# 08-I225-1.net
KiCad netlist of a schematic drawn in Altium Designer
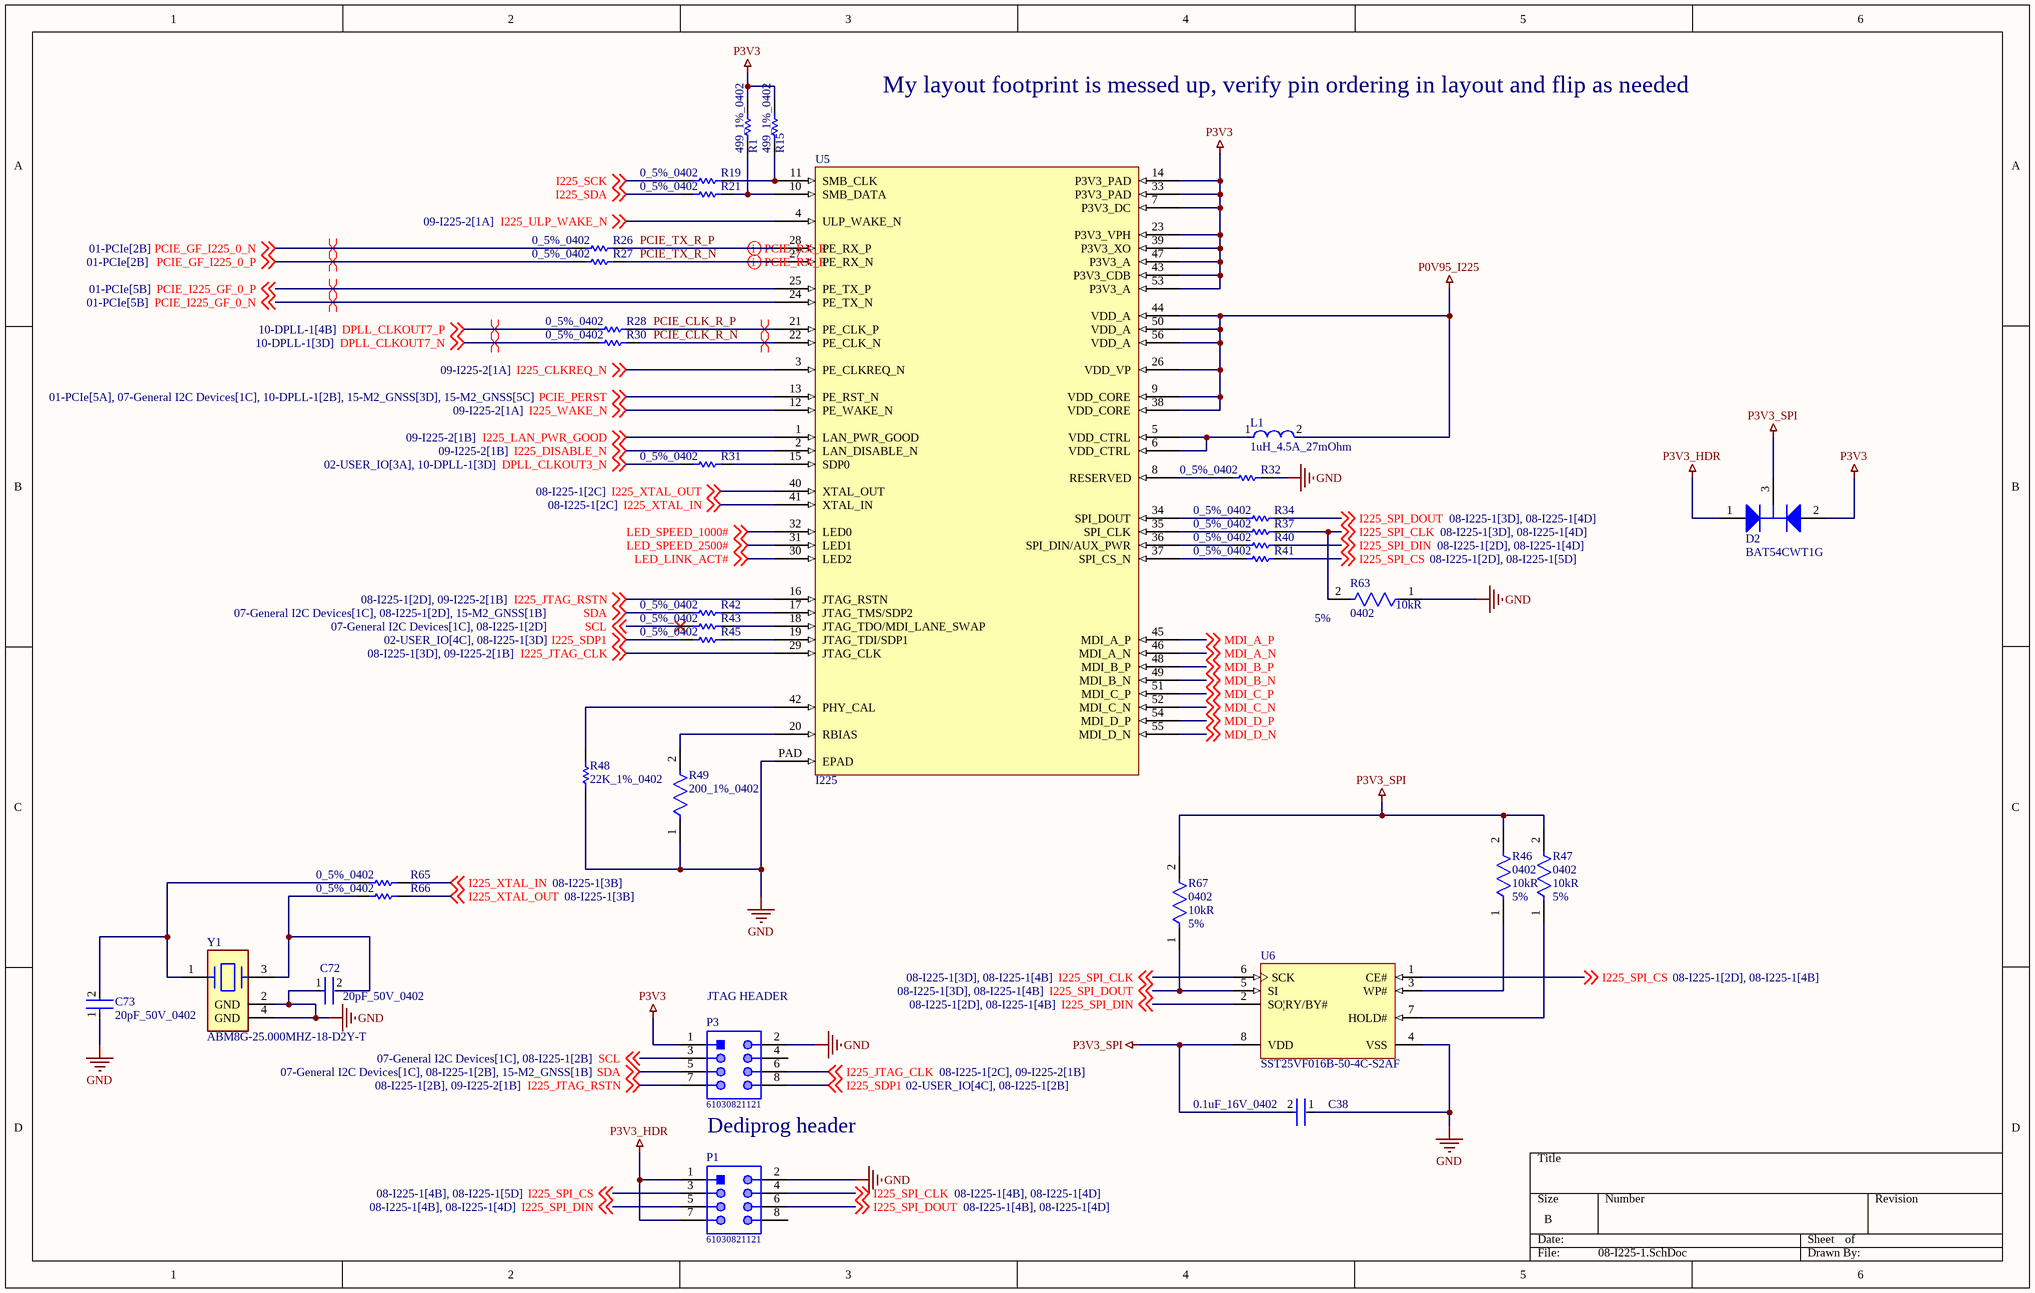
[diagram p0: 08-I225-1.SchDoc]

(export (version "E")
  (design (tool "Eeschema 10.0.6"))
  (components
    (comp (ref "C38")
      (value "0.1uF_16V_0402")
      (footprint "FP-GRM15-MFG")
      (description "CAP CER 0.1UF 16V X7R 0402")
      (fields (field (name "MANUFACTURER PART NUMBER") "GRM155R71C104KA88D") (field (name "TOLERANCE") "10%"))
      (libsource (lib "Altium Content Vault") (part "236180d848d6139a670b325ea6854c9"))
    )
    (comp (ref "C72")
      (value "20pF_50V_0402")
      (footprint "FP-C0402-BB-MFG")
      (description "CAP CER 20PF 50V 5% NP0 0402")
      (fields
        (field (name "MANUFACTURER PART NUMBER") "C0402C200J5GACTU")
        (field (name "OCTOPART") "https://octopart.com/c0402c200j5gactu-kemet-9143900")
      )
      (libsource (lib "Altium Content Vault") (part "b4654b650e69147ec39a6b967a45e02"))
    )
    (comp (ref "C73")
      (value "20pF_50V_0402")
      (footprint "FP-C0402-BB-MFG")
      (description "CAP CER 20PF 50V 5% NP0 0402")
      (fields
        (field (name "MANUFACTURER PART NUMBER") "C0402C200J5GACTU")
        (field (name "OCTOPART") "https://octopart.com/c0402c200j5gactu-kemet-9143900")
      )
      (libsource (lib "Altium Content Vault") (part "b4654b650e69147ec39a6b967a45e02"))
    )
    (comp (ref "D2")
      (value "BAT54CWT1G")
      (footprint "ONSC-SOT-323-3-419-04_V")
      (description "Dual Series Cathode Schottky Barrier Diodes, 3-Pin SOT-323, Pb-Free, Tape and Reel")
      (fields (field (name "MANUFACTURER") "On Semiconductor"))
      (libsource (lib "Altium Content Vault") (part "ONSC-D-A1A2K3-3"))
    )
    (comp (ref "L1")
      (value "1uH_4.5A_27mOhm")
      (footprint "FP-IHLP-1616BZ-FP_1_8545x-MFG")
      (description "Fixed Inductors Commercial Low DCR Series SMT 1uH 4.5A 27mΩ 20%")
      (fields (field (name "TOLERANCE") "20%"))
      (libsource (lib "Altium Content Vault") (part "725321dda6339637d4d059423bc1c3c"))
    )
    (comp (ref "P1")
      (value "61030821121")
      (footprint "61030821121")
      (description "SMT Vertical Pin Header WR-PHD, Pitch 2.54 mm, Dual Row, 8 pins")
      (fields (field (name "MANUFACTURER") "Wurth Elektronik") (field (name "PUBLISHER") "WurthElektronik"))
      (libsource (lib "Altium Content Vault") (part "WE-CN-2P-M-R8"))
    )
    (comp (ref "P3")
      (value "61030821121")
      (footprint "61030821121")
      (description "SMT Vertical Pin Header WR-PHD, Pitch 2.54 mm, Dual Row, 8 pins")
      (fields (field (name "MANUFACTURER") "Wurth Elektronik") (field (name "PUBLISHER") "WurthElektronik"))
      (libsource (lib "Altium Content Vault") (part "WE-CN-2P-M-R8"))
    )
    (comp (ref "R1")
      (value "499_1%_0402")
      (footprint "RESC1005X40X25LL05T05")
      (fields (field (name "MANUFACTURER") "Panasonic") (field (name "PART NUMBER") "ERJ-2RKF4990X"))
      (libsource (lib "Altium Content Vault") (part "RES"))
    )
    (comp (ref "R15")
      (value "499_1%_0402")
      (footprint "RESC1005X40X25LL05T05")
      (fields (field (name "MANUFACTURER") "Panasonic") (field (name "PART NUMBER") "ERJ-2RKF4990X"))
      (libsource (lib "Altium Content Vault") (part "RES"))
    )
    (comp (ref "R19")
      (value "0_5%_0402")
      (footprint "RESC1005X40X25LL10T10")
      (fields (field (name "MANUFACTURER") "KOA Speer") (field (name "PART NUMBER") "RK73Z1ETTP"))
      (libsource (lib "Altium Content Vault") (part "RES"))
    )
    (comp (ref "R21")
      (value "0_5%_0402")
      (footprint "RESC1005X40X25LL10T10")
      (fields (field (name "MANUFACTURER") "KOA Speer") (field (name "PART NUMBER") "RK73Z1ETTP"))
      (libsource (lib "Altium Content Vault") (part "RES"))
    )
    (comp (ref "R26")
      (value "0_5%_0402")
      (footprint "RESC1005X40X25LL10T10")
      (fields (field (name "MANUFACTURER") "KOA Speer") (field (name "PART NUMBER") "RK73Z1ETTP"))
      (libsource (lib "Altium Content Vault") (part "RES"))
    )
    (comp (ref "R27")
      (value "0_5%_0402")
      (footprint "RESC1005X40X25LL10T10")
      (fields (field (name "MANUFACTURER") "KOA Speer") (field (name "PART NUMBER") "RK73Z1ETTP"))
      (libsource (lib "Altium Content Vault") (part "RES"))
    )
    (comp (ref "R28")
      (value "0_5%_0402")
      (footprint "RESC1005X40X25LL10T10")
      (fields (field (name "MANUFACTURER") "KOA Speer") (field (name "PART NUMBER") "RK73Z1ETTP"))
      (libsource (lib "Altium Content Vault") (part "RES"))
    )
    (comp (ref "R30")
      (value "0_5%_0402")
      (footprint "RESC1005X40X25LL10T10")
      (fields (field (name "MANUFACTURER") "KOA Speer") (field (name "PART NUMBER") "RK73Z1ETTP"))
      (libsource (lib "Altium Content Vault") (part "RES"))
    )
    (comp (ref "R31")
      (value "0_5%_0402")
      (footprint "RESC1005X40X25LL10T10")
      (fields (field (name "MANUFACTURER") "KOA Speer") (field (name "PART NUMBER") "RK73Z1ETTP"))
      (libsource (lib "Altium Content Vault") (part "RES"))
    )
    (comp (ref "R32")
      (value "0_5%_0402")
      (footprint "RESC1005X40X25LL10T10")
      (fields (field (name "MANUFACTURER") "KOA Speer") (field (name "PART NUMBER") "RK73Z1ETTP"))
      (libsource (lib "Altium Content Vault") (part "RES"))
    )
    (comp (ref "R34")
      (value "0_5%_0402")
      (footprint "RESC1005X40X25LL10T10")
      (fields (field (name "MANUFACTURER") "KOA Speer") (field (name "PART NUMBER") "RK73Z1ETTP"))
      (libsource (lib "Altium Content Vault") (part "RES"))
    )
    (comp (ref "R37")
      (value "0_5%_0402")
      (footprint "RESC1005X40X25LL10T10")
      (fields (field (name "MANUFACTURER") "KOA Speer") (field (name "PART NUMBER") "RK73Z1ETTP"))
      (libsource (lib "Altium Content Vault") (part "RES"))
    )
    (comp (ref "R40")
      (value "0_5%_0402")
      (footprint "RESC1005X40X25LL10T10")
      (fields (field (name "MANUFACTURER") "KOA Speer") (field (name "PART NUMBER") "RK73Z1ETTP"))
      (libsource (lib "Altium Content Vault") (part "RES"))
    )
    (comp (ref "R41")
      (value "0_5%_0402")
      (footprint "RESC1005X40X25LL10T10")
      (fields (field (name "MANUFACTURER") "KOA Speer") (field (name "PART NUMBER") "RK73Z1ETTP"))
      (libsource (lib "Altium Content Vault") (part "RES"))
    )
    (comp (ref "R42")
      (value "0_5%_0402")
      (footprint "RESC1005X40X25LL10T10")
      (fields (field (name "MANUFACTURER") "KOA Speer") (field (name "PART NUMBER") "RK73Z1ETTP"))
      (libsource (lib "Altium Content Vault") (part "RES"))
    )
    (comp (ref "R43")
      (value "0_5%_0402")
      (footprint "RESC1005X40X25LL10T10")
      (fields (field (name "MANUFACTURER") "KOA Speer") (field (name "PART NUMBER") "RK73Z1ETTP"))
      (libsource (lib "Altium Content Vault") (part "RES"))
    )
    (comp (ref "R45")
      (value "0_5%_0402")
      (footprint "RESC1005X40X25LL10T10")
      (fields (field (name "MANUFACTURER") "KOA Speer") (field (name "PART NUMBER") "RK73Z1ETTP"))
      (libsource (lib "Altium Content Vault") (part "RES"))
    )
    (comp (ref "R46")
      (value "CRCW040210K0JNED")
      (footprint "FP-CRCW0402-e3-IPC_B")
      (description "RES Thick Film, 10kΩ, 5%, 0.063W, 200ppm/°C, 0402")
      (fields
        (field (name "CASE/PACKAGE") "0402")
        (field (name "RESISTANCE") "10kR")
        (field (name "TOLERANCE") "5%")
      )
      (libsource (lib "Altium Content Vault") (part "1029c3af85768c4190bb7ad29bc67b5"))
    )
    (comp (ref "R47")
      (value "CRCW040210K0JNED")
      (footprint "FP-CRCW0402-e3-IPC_B")
      (description "RES Thick Film, 10kΩ, 5%, 0.063W, 200ppm/°C, 0402")
      (fields
        (field (name "CASE/PACKAGE") "0402")
        (field (name "RESISTANCE") "10kR")
        (field (name "TOLERANCE") "5%")
      )
      (libsource (lib "Altium Content Vault") (part "1029c3af85768c4190bb7ad29bc67b5"))
    )
    (comp (ref "R48")
      (value "22K_1%_0402")
      (footprint "RESC1005X40X25NL05T05")
      (fields (field (name "PART NUMBER") "CRCW040222K0FKED") (field (name "MANUFACTURER") "Vishay Dale"))
      (libsource (lib "Altium Content Vault") (part "RES"))
    )
    (comp (ref "R49")
      (value "200_1%_0402")
      (footprint "FP-CRCW0402-e3-IPC_C")
      (description "RES Thick Film, 200Ω, 1%, 0.063W, 100ppm/°C, 0402")
      (fields (field (name "TOLERANCE") "1%"))
      (libsource (lib "Altium Content Vault") (part "1029c3af85768c4190bb7ad29bc67b5"))
    )
    (comp (ref "R63")
      (value "CRCW040210K0JNED")
      (footprint "FP-CRCW0402-e3-IPC_B")
      (description "RES Thick Film, 10kΩ, 5%, 0.063W, 200ppm/°C, 0402")
      (fields
        (field (name "CASE/PACKAGE") "0402")
        (field (name "RESISTANCE") "10kR")
        (field (name "TOLERANCE") "5%")
      )
      (libsource (lib "Altium Content Vault") (part "1029c3af85768c4190bb7ad29bc67b5"))
    )
    (comp (ref "R65")
      (value "0_5%_0402")
      (footprint "RESC1005X40X25LL10T10")
      (fields (field (name "MANUFACTURER") "KOA Speer") (field (name "PART NUMBER") "RK73Z1ETTP"))
      (libsource (lib "Altium Content Vault") (part "RES"))
    )
    (comp (ref "R66")
      (value "0_5%_0402")
      (footprint "RESC1005X40X25LL10T10")
      (fields (field (name "MANUFACTURER") "KOA Speer") (field (name "PART NUMBER") "RK73Z1ETTP"))
      (libsource (lib "Altium Content Vault") (part "RES"))
    )
    (comp (ref "R67")
      (value "CRCW040210K0JNED")
      (footprint "FP-CRCW0402-e3-IPC_B")
      (description "RES Thick Film, 10kΩ, 5%, 0.063W, 200ppm/°C, 0402")
      (fields
        (field (name "CASE/PACKAGE") "0402")
        (field (name "RESISTANCE") "10kR")
        (field (name "TOLERANCE") "5%")
      )
      (libsource (lib "Altium Content Vault") (part "1029c3af85768c4190bb7ad29bc67b5"))
    )
    (comp (ref "U5") (value "I225") (footprint "I225 QFN56") (libsource (lib "TimeStick_Lib") (part "I225")))
    (comp (ref "U6")
      (value "SST25VF016B-50-4C-S2AF")
      (footprint "MCHP-SOIC-S2A8_M")
      (description "16 Mbit SPI Serial Flash, 2.7 to 3.6 V, 50 MHz, 0 to 70 degC, 8-pin SOIC (S2A8), Tube")
      (fields (field (name "MANUFACTURER") "Microchip"))
      (libsource (lib "Altium Content Vault") (part "MCHP-SST25VFXXXB-SOIX-8"))
    )
    (comp (ref "Y1")
      (value "ABM8G-25.000MHZ-18-D2Y-T")
      (footprint "FP-ABM8G-MFG")
      (description "CRYSTAL 25.0000MHZ 18PF SMD")
      (fields
        (field (name "MANUFACTURER") "Abracon")
        (field (name "OCTOPART") "https://octopart.com/abm8g-25.000mhz-18-d2y-t-abracon-12676602")
      )
      (libsource (lib "Altium Content Vault") (part "82af6c543cb7a88a4cbd02a3a01c293"))
    )
  )
  (nets
    (net (code "1") (name "/PCIE_CLK_R_N") (class "Default")
      (node (ref "R30") (pin "2") (pinfunction "2_2") (pintype "passive"))
      (node (ref "U5") (pin "22") (pinfunction "PE_CLK_N_22") (pintype "input"))
    )
    (net (code "2") (name "/PCIE_CLK_R_P") (class "Default")
      (node (ref "R28") (pin "2") (pinfunction "2_2") (pintype "passive"))
      (node (ref "U5") (pin "21") (pinfunction "PE_CLK_P_21") (pintype "input"))
    )
    (net (code "3") (name "/PCIE_TX_R_N") (class "Default")
      (node (ref "R27") (pin "2") (pinfunction "2_2") (pintype "passive"))
      (node (ref "U5") (pin "27") (pinfunction "PE_RX_N_27") (pintype "input"))
    )
    (net (code "4") (name "/PCIE_TX_R_P") (class "Default")
      (node (ref "R26") (pin "2") (pinfunction "2_2") (pintype "passive"))
      (node (ref "U5") (pin "28") (pinfunction "PE_RX_P_28") (pintype "input"))
    )
    (net (code "5") (name "DPLL_CLKOUT3_N") (class "Default")
      (node (ref "R31") (pin "1") (pinfunction "1_1") (pintype "passive"))
    )
    (net (code "6") (name "DPLL_CLKOUT7_N") (class "Default")
      (node (ref "R30") (pin "1") (pinfunction "1_1") (pintype "passive"))
    )
    (net (code "7") (name "DPLL_CLKOUT7_P") (class "Default")
      (node (ref "R28") (pin "1") (pinfunction "1_1") (pintype "passive"))
    )
    (net (code "8") (name "GND") (class "Default")
      (node (ref "C38") (pin "1") (pinfunction "1_1") (pintype "passive"))
      (node (ref "C72") (pin "1") (pinfunction "1_1") (pintype "passive"))
      (node (ref "C73") (pin "1") (pinfunction "1_1") (pintype "passive"))
      (node (ref "P1") (pin "2") (pinfunction "2_2") (pintype "passive"))
      (node (ref "P3") (pin "2") (pinfunction "2_2") (pintype "passive"))
      (node (ref "R32") (pin "2") (pinfunction "2_2") (pintype "passive"))
      (node (ref "R48") (pin "1") (pinfunction "1_1") (pintype "passive"))
      (node (ref "R49") (pin "1") (pinfunction "1_1") (pintype "passive"))
      (node (ref "R63") (pin "1") (pinfunction "1_1") (pintype "passive"))
      (node (ref "U5") (pin "PAD") (pinfunction "EPAD_PAD") (pintype "input"))
      (node (ref "U6") (pin "4") (pinfunction "VSS_4") (pintype "power_in"))
      (node (ref "Y1") (pin "2") (pinfunction "GND_2") (pintype "power_in"))
      (node (ref "Y1") (pin "4") (pinfunction "GND_4") (pintype "power_in"))
    )
    (net (code "9") (name "I225_CLKREQ_N") (class "Default")
      (node (ref "U5") (pin "3") (pinfunction "PE_CLKREQ_N_3") (pintype "input"))
    )
    (net (code "10") (name "I225_DISABLE_N") (class "Default")
      (node (ref "U5") (pin "2") (pinfunction "LAN_DISABLE_N_2") (pintype "input"))
    )
    (net (code "11") (name "I225_JTAG_CLK") (class "Default")
      (node (ref "P3") (pin "6") (pinfunction "6_6") (pintype "passive"))
      (node (ref "U5") (pin "29") (pinfunction "JTAG_CLK_29") (pintype "input"))
    )
    (net (code "12") (name "I225_JTAG_RSTN") (class "Default")
      (node (ref "P3") (pin "7") (pinfunction "7_7") (pintype "passive"))
      (node (ref "U5") (pin "16") (pinfunction "JTAG_RSTN_16") (pintype "input"))
    )
    (net (code "13") (name "I225_LAN_PWR_GOOD") (class "Default")
      (node (ref "U5") (pin "1") (pinfunction "LAN_PWR_GOOD_1") (pintype "input"))
    )
    (net (code "14") (name "I225_SCK") (class "Default")
      (node (ref "R19") (pin "1") (pinfunction "1_1") (pintype "passive"))
    )
    (net (code "15") (name "I225_SDA") (class "Default")
      (node (ref "R21") (pin "1") (pinfunction "1_1") (pintype "passive"))
    )
    (net (code "16") (name "I225_SDP1") (class "Default")
      (node (ref "P3") (pin "8") (pinfunction "8_8") (pintype "passive"))
      (node (ref "R45") (pin "1") (pinfunction "1_1") (pintype "passive"))
    )
    (net (code "17") (name "I225_SPI_CLK") (class "Default")
      (node (ref "P1") (pin "4") (pinfunction "4_4") (pintype "passive"))
      (node (ref "R37") (pin "2") (pinfunction "2_2") (pintype "passive"))
      (node (ref "R63") (pin "2") (pinfunction "2_2") (pintype "passive"))
      (node (ref "U6") (pin "6") (pinfunction "SCK_6") (pintype "input"))
    )
    (net (code "18") (name "I225_SPI_CS") (class "Default")
      (node (ref "P1") (pin "3") (pinfunction "3_3") (pintype "passive"))
      (node (ref "R41") (pin "2") (pinfunction "2_2") (pintype "passive"))
      (node (ref "U6") (pin "1") (pinfunction "CE#_1") (pintype "input"))
    )
    (net (code "19") (name "I225_SPI_DIN") (class "Default")
      (node (ref "P1") (pin "5") (pinfunction "5_5") (pintype "passive"))
      (node (ref "R40") (pin "2") (pinfunction "2_2") (pintype "passive"))
      (node (ref "U6") (pin "2") (pinfunction "SO¦RY/BY#_2") (pintype "tri_state"))
    )
    (net (code "20") (name "I225_SPI_DOUT") (class "Default")
      (node (ref "P1") (pin "6") (pinfunction "6_6") (pintype "passive"))
      (node (ref "R34") (pin "2") (pinfunction "2_2") (pintype "passive"))
      (node (ref "R67") (pin "1") (pinfunction "1_1") (pintype "passive"))
      (node (ref "U6") (pin "5") (pinfunction "SI_5") (pintype "input"))
    )
    (net (code "21") (name "I225_ULP_WAKE_N") (class "Default")
      (node (ref "U5") (pin "4") (pinfunction "ULP_WAKE_N_4") (pintype "input"))
    )
    (net (code "22") (name "I225_WAKE_N") (class "Default")
      (node (ref "U5") (pin "12") (pinfunction "PE_WAKE_N_12") (pintype "input"))
    )
    (net (code "23") (name "I225_XTAL_IN") (class "Default")
      (node (ref "R65") (pin "2") (pinfunction "2_2") (pintype "passive"))
      (node (ref "U5") (pin "41") (pinfunction "XTAL_IN_41") (pintype "input"))
    )
    (net (code "24") (name "I225_XTAL_OUT") (class "Default")
      (node (ref "R66") (pin "2") (pinfunction "2_2") (pintype "passive"))
      (node (ref "U5") (pin "40") (pinfunction "XTAL_OUT_40") (pintype "input"))
    )
    (net (code "25") (name "LED_LINK_ACT#") (class "Default")
      (node (ref "U5") (pin "30") (pinfunction "LED2_30") (pintype "input"))
    )
    (net (code "26") (name "LED_SPEED_1000#") (class "Default")
      (node (ref "U5") (pin "32") (pinfunction "LED0_32") (pintype "input"))
    )
    (net (code "27") (name "LED_SPEED_2500#") (class "Default")
      (node (ref "U5") (pin "31") (pinfunction "LED1_31") (pintype "input"))
    )
    (net (code "28") (name "MDI_A_N") (class "Default")
      (node (ref "U5") (pin "46") (pinfunction "MDI_A_N_46") (pintype "input"))
    )
    (net (code "29") (name "MDI_A_P") (class "Default")
      (node (ref "U5") (pin "45") (pinfunction "MDI_A_P_45") (pintype "input"))
    )
    (net (code "30") (name "MDI_B_N") (class "Default")
      (node (ref "U5") (pin "49") (pinfunction "MDI_B_N_49") (pintype "input"))
    )
    (net (code "31") (name "MDI_B_P") (class "Default")
      (node (ref "U5") (pin "48") (pinfunction "MDI_B_P_48") (pintype "input"))
    )
    (net (code "32") (name "MDI_C_N") (class "Default")
      (node (ref "U5") (pin "52") (pinfunction "MDI_C_N_52") (pintype "input"))
    )
    (net (code "33") (name "MDI_C_P") (class "Default")
      (node (ref "U5") (pin "51") (pinfunction "MDI_C_P_51") (pintype "input"))
    )
    (net (code "34") (name "MDI_D_N") (class "Default")
      (node (ref "U5") (pin "55") (pinfunction "MDI_D_N_55") (pintype "input"))
    )
    (net (code "35") (name "MDI_D_P") (class "Default")
      (node (ref "U5") (pin "54") (pinfunction "MDI_D_P_54") (pintype "input"))
    )
    (net (code "36") (name "Net-(C72-Pad2)") (class "Default")
      (node (ref "C72") (pin "2") (pinfunction "2_2") (pintype "passive"))
      (node (ref "R66") (pin "1") (pinfunction "1_1") (pintype "passive"))
      (node (ref "Y1") (pin "3") (pinfunction "3_3") (pintype "passive"))
    )
    (net (code "37") (name "Net-(C73-Pad2)") (class "Default")
      (node (ref "C73") (pin "2") (pinfunction "2_2") (pintype "passive"))
      (node (ref "R65") (pin "1") (pinfunction "1_1") (pintype "passive"))
      (node (ref "Y1") (pin "1") (pinfunction "1_1") (pintype "passive"))
    )
    (net (code "38") (name "Net-(L1-Pad1)") (class "Default")
      (node (ref "L1") (pin "1") (pinfunction "1_1") (pintype "passive"))
      (node (ref "U5") (pin "5") (pinfunction "VDD_CTRL_5") (pintype "input"))
      (node (ref "U5") (pin "6") (pinfunction "VDD_CTRL_6") (pintype "input"))
    )
    (net (code "39") (name "Net-(U5-JTAG_TDI{slash}SDP1)") (class "Default")
      (node (ref "R45") (pin "2") (pinfunction "2_2") (pintype "passive"))
      (node (ref "U5") (pin "19") (pinfunction "JTAG_TDI/SDP1_19") (pintype "input"))
    )
    (net (code "40") (name "Net-(U5-JTAG_TDO{slash}MDI_LANE_SWAP)") (class "Default")
      (node (ref "R43") (pin "2") (pinfunction "2_2") (pintype "passive"))
      (node (ref "U5") (pin "18") (pinfunction "JTAG_TDO/MDI_LANE_SWAP_18") (pintype "input"))
    )
    (net (code "41") (name "Net-(U5-JTAG_TMS{slash}SDP2)") (class "Default")
      (node (ref "R42") (pin "2") (pinfunction "2_2") (pintype "passive"))
      (node (ref "U5") (pin "17") (pinfunction "JTAG_TMS/SDP2_17") (pintype "input"))
    )
    (net (code "42") (name "Net-(U5-PHY_CAL)") (class "Default")
      (node (ref "R48") (pin "2") (pinfunction "2_2") (pintype "passive"))
      (node (ref "U5") (pin "42") (pinfunction "PHY_CAL_42") (pintype "input"))
    )
    (net (code "43") (name "Net-(U5-RBIAS)") (class "Default")
      (node (ref "R49") (pin "2") (pinfunction "2_2") (pintype "passive"))
      (node (ref "U5") (pin "20") (pinfunction "RBIAS_20") (pintype "input"))
    )
    (net (code "44") (name "Net-(U5-RESERVED)") (class "Default")
      (node (ref "R32") (pin "1") (pinfunction "1_1") (pintype "passive"))
      (node (ref "U5") (pin "8") (pinfunction "RESERVED_8") (pintype "input"))
    )
    (net (code "45") (name "Net-(U5-SDP0)") (class "Default")
      (node (ref "R31") (pin "2") (pinfunction "2_2") (pintype "passive"))
      (node (ref "U5") (pin "15") (pinfunction "SDP0_15") (pintype "input"))
    )
    (net (code "46") (name "Net-(U5-SMB_CLK)") (class "Default")
      (node (ref "R15") (pin "1") (pinfunction "1_1") (pintype "passive"))
      (node (ref "R19") (pin "2") (pinfunction "2_2") (pintype "passive"))
      (node (ref "U5") (pin "11") (pinfunction "SMB_CLK_11") (pintype "input"))
    )
    (net (code "47") (name "Net-(U5-SMB_DATA)") (class "Default")
      (node (ref "R1") (pin "1") (pinfunction "1_1") (pintype "passive"))
      (node (ref "R21") (pin "2") (pinfunction "2_2") (pintype "passive"))
      (node (ref "U5") (pin "10") (pinfunction "SMB_DATA_10") (pintype "input"))
    )
    (net (code "48") (name "Net-(U5-SPI_CLK)") (class "Default")
      (node (ref "R37") (pin "1") (pinfunction "1_1") (pintype "passive"))
      (node (ref "U5") (pin "35") (pinfunction "SPI_CLK_35") (pintype "input"))
    )
    (net (code "49") (name "Net-(U5-SPI_CS_N)") (class "Default")
      (node (ref "R41") (pin "1") (pinfunction "1_1") (pintype "passive"))
      (node (ref "U5") (pin "37") (pinfunction "SPI_CS_N_37") (pintype "input"))
    )
    (net (code "50") (name "Net-(U5-SPI_DIN{slash}AUX_PWR)") (class "Default")
      (node (ref "R40") (pin "1") (pinfunction "1_1") (pintype "passive"))
      (node (ref "U5") (pin "36") (pinfunction "SPI_DIN/AUX_PWR_36") (pintype "input"))
    )
    (net (code "51") (name "Net-(U5-SPI_DOUT)") (class "Default")
      (node (ref "R34") (pin "1") (pinfunction "1_1") (pintype "passive"))
      (node (ref "U5") (pin "34") (pinfunction "SPI_DOUT_34") (pintype "input"))
    )
    (net (code "52") (name "Net-(U6-HOLD#)") (class "Default")
      (node (ref "R47") (pin "1") (pinfunction "1_1") (pintype "passive"))
      (node (ref "U6") (pin "7") (pinfunction "HOLD#_7") (pintype "input"))
    )
    (net (code "53") (name "Net-(U6-WP#)") (class "Default")
      (node (ref "R46") (pin "1") (pinfunction "1_1") (pintype "passive"))
      (node (ref "U6") (pin "3") (pinfunction "WP#_3") (pintype "input"))
    )
    (net (code "54") (name "P0V95_I225") (class "Default")
      (node (ref "L1") (pin "2") (pinfunction "2_2") (pintype "passive"))
      (node (ref "U5") (pin "26") (pinfunction "VDD_VP_26") (pintype "input"))
      (node (ref "U5") (pin "38") (pinfunction "VDD_CORE_38") (pintype "input"))
      (node (ref "U5") (pin "44") (pinfunction "VDD_A_44") (pintype "input"))
      (node (ref "U5") (pin "50") (pinfunction "VDD_A_50") (pintype "input"))
      (node (ref "U5") (pin "56") (pinfunction "VDD_A_56") (pintype "input"))
      (node (ref "U5") (pin "9") (pinfunction "VDD_CORE_9") (pintype "input"))
    )
    (net (code "55") (name "P3V3") (class "Default")
      (node (ref "D2") (pin "2") (pinfunction "A2_2") (pintype "passive"))
      (node (ref "P3") (pin "1") (pinfunction "1_1") (pintype "passive"))
      (node (ref "R1") (pin "2") (pinfunction "2_2") (pintype "passive"))
      (node (ref "R15") (pin "2") (pinfunction "2_2") (pintype "passive"))
      (node (ref "U5") (pin "14") (pinfunction "P3V3_PAD_14") (pintype "input"))
      (node (ref "U5") (pin "23") (pinfunction "P3V3_VPH_23") (pintype "input"))
      (node (ref "U5") (pin "33") (pinfunction "P3V3_PAD_33") (pintype "input"))
      (node (ref "U5") (pin "39") (pinfunction "P3V3_XO_39") (pintype "input"))
      (node (ref "U5") (pin "43") (pinfunction "P3V3_CDB_43") (pintype "input"))
      (node (ref "U5") (pin "47") (pinfunction "P3V3_A_47") (pintype "input"))
      (node (ref "U5") (pin "53") (pinfunction "P3V3_A_53") (pintype "input"))
      (node (ref "U5") (pin "7") (pinfunction "P3V3_DC_7") (pintype "input"))
    )
    (net (code "56") (name "P3V3_HDR") (class "Default")
      (node (ref "D2") (pin "1") (pinfunction "A1_1") (pintype "passive"))
      (node (ref "P1") (pin "1") (pinfunction "1_1") (pintype "passive"))
      (node (ref "P1") (pin "7") (pinfunction "7_7") (pintype "passive"))
    )
    (net (code "57") (name "P3V3_SPI") (class "Default")
      (node (ref "C38") (pin "2") (pinfunction "2_2") (pintype "passive"))
      (node (ref "D2") (pin "3") (pinfunction "K_3") (pintype "passive"))
      (node (ref "R46") (pin "2") (pinfunction "2_2") (pintype "passive"))
      (node (ref "R47") (pin "2") (pinfunction "2_2") (pintype "passive"))
      (node (ref "R67") (pin "2") (pinfunction "2_2") (pintype "passive"))
      (node (ref "U6") (pin "8") (pinfunction "VDD_8") (pintype "power_in"))
    )
    (net (code "58") (name "PCIE_GF_I225_0_N") (class "Default")
      (node (ref "R26") (pin "1") (pinfunction "1_1") (pintype "passive"))
    )
    (net (code "59") (name "PCIE_GF_I225_0_P") (class "Default")
      (node (ref "R27") (pin "1") (pinfunction "1_1") (pintype "passive"))
    )
    (net (code "60") (name "PCIE_I225_GF_0_N") (class "Default")
      (node (ref "U5") (pin "24") (pinfunction "PE_TX_N_24") (pintype "input"))
    )
    (net (code "61") (name "PCIE_I225_GF_0_P") (class "Default")
      (node (ref "U5") (pin "25") (pinfunction "PE_TX_P_25") (pintype "input"))
    )
    (net (code "62") (name "PCIE_PERST") (class "Default")
      (node (ref "U5") (pin "13") (pinfunction "PE_RST_N_13") (pintype "input"))
    )
    (net (code "63") (name "SCL") (class "Default")
      (node (ref "P3") (pin "3") (pinfunction "3_3") (pintype "passive"))
      (node (ref "R43") (pin "1") (pinfunction "1_1") (pintype "passive"))
    )
    (net (code "64") (name "SDA") (class "Default")
      (node (ref "P3") (pin "5") (pinfunction "5_5") (pintype "passive"))
      (node (ref "R42") (pin "1") (pinfunction "1_1") (pintype "passive"))
    )
    (net (code "65") (name "unconnected-(P1-Pad8)") (class "Default")
      (node (ref "P1") (pin "8") (pinfunction "8_8") (pintype "passive"))
    )
    (net (code "66") (name "unconnected-(P3-Pad4)") (class "Default")
      (node (ref "P3") (pin "4") (pinfunction "4_4") (pintype "passive"))
    )
  )
)
